# Power_Discrete_-_Features.net
KiCad netlist of a schematic drawn in Altium Designer
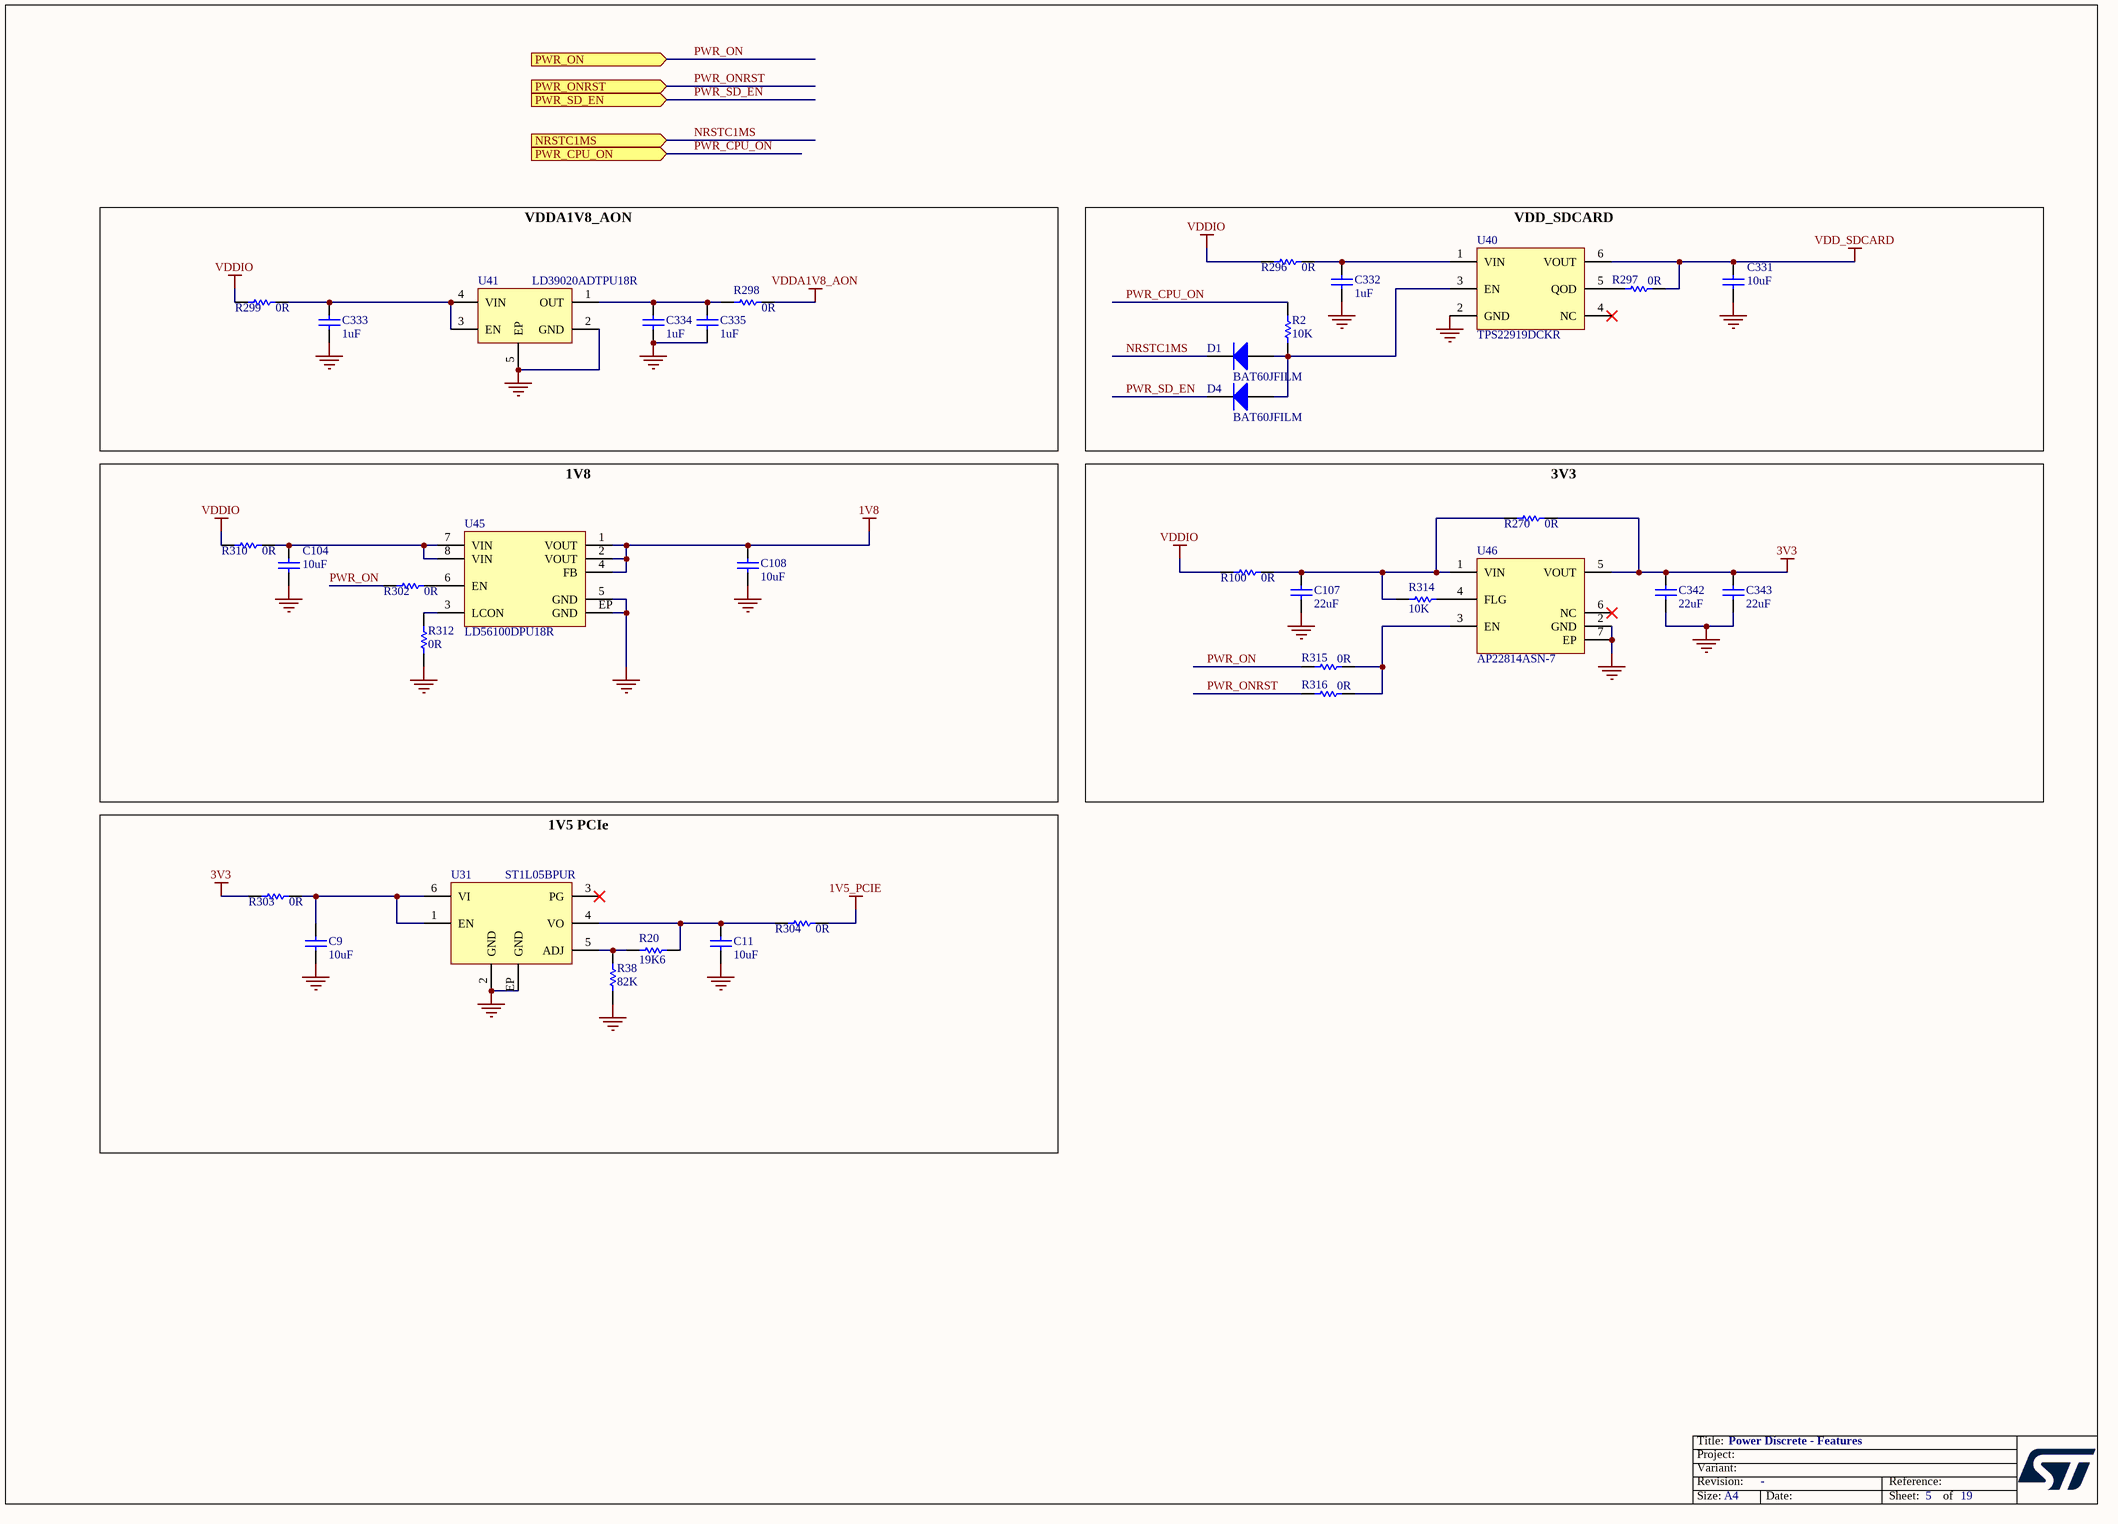
[diagram p0: Power_Discrete - Features.SchDoc]

(export (version "E")
  (design (tool "Eeschema 10.0.6"))
  (components
    (comp (ref "C9")
      (value "10uF")
      (footprint "C0402")
      (description "Capacitor, MLCC, 10uF, 10V, X5R, +/-20%, 0402, T=0.5mm")
      (fields (field (name "INTERNAL_PART_NUMBER") "MCD-01532") (field (name "MANUFACTURER") "MURATA"))
      (libsource (lib "MCD_PARTS_database") (part "Capacitor"))
    )
    (comp (ref "C11")
      (value "10uF")
      (footprint "C0402")
      (description "Capacitor, MLCC, 10uF, 10V, X5R, +/-20%, 0402, T=0.5mm")
      (fields (field (name "INTERNAL_PART_NUMBER") "MCD-01532") (field (name "MANUFACTURER") "MURATA"))
      (libsource (lib "MCD_PARTS_database") (part "Capacitor"))
    )
    (comp (ref "C104")
      (value "10uF")
      (footprint "C0603")
      (description "Capacitor, MLCC, 10uF, 10V, X5R, +/-10%, 0603, T=0,8mm")
      (fields
        (field (name "INTERNAL_PART_NUMBER") "MCD-00099")
        (field (name "MANUFACTURER_PART_NUMBER") "GRM188R61A106KE69D")
      )
      (libsource (lib "MCD_PARTS_database") (part "Capacitor"))
    )
    (comp (ref "C107")
      (value "22uF")
      (footprint "C0603")
      (description "Capacitor, MLCC, 22uF, 6V3, X5R, +/-20%, 0603, T=0,8mm")
      (fields
        (field (name "INTERNAL_PART_NUMBER") "MCD-00100")
        (field (name "MANUFACTURER_PART_NUMBER") "GRM188R60J226MEA0J")
      )
      (libsource (lib "MCD_PARTS_database") (part "Capacitor"))
    )
    (comp (ref "C108")
      (value "10uF")
      (footprint "C0603")
      (description "Capacitor, MLCC, 10uF, 10V, X5R, +/-10%, 0603, T=0.8mm")
      (fields (field (name "INTERNAL_PART_NUMBER") "MCD-00099") (field (name "MANUFACTURER") "MURATA"))
      (libsource (lib "MCD_PARTS_database") (part "Capacitor"))
    )
    (comp (ref "C331")
      (value "10uF")
      (footprint "C0603")
      (description "Capacitor, MLCC, 10uF, 10V, X5R, +/-10%, 0603, T=0,8mm")
      (fields
        (field (name "INTERNAL_PART_NUMBER") "MCD-00099")
        (field (name "MANUFACTURER_PART_NUMBER") "GRM188R61A106KE69D")
      )
      (libsource (lib "MCD_PARTS_database") (part "Capacitor"))
    )
    (comp (ref "C332")
      (value "1uF")
      (footprint "C0402")
      (description "Capacitor, MLCC, 1uF, 25V, X5R, +/-10%, 0402, T=0,5mm")
      (fields
        (field (name "INTERNAL_PART_NUMBER") "MCD-00095")
        (field (name "MANUFACTURER_PART_NUMBER") "GRM155R61E105KA12")
      )
      (libsource (lib "MCD_PARTS_database") (part "Capacitor"))
    )
    (comp (ref "C333")
      (value "1uF")
      (footprint "C0402")
      (description "Capacitor, MLCC, 1uF, 25V, X5R, +/-10%, 0402, T=0.5mm")
      (fields (field (name "INTERNAL_PART_NUMBER") "MCD-00095") (field (name "MANUFACTURER") "MURATA"))
      (libsource (lib "MCD_PARTS_database") (part "Capacitor"))
    )
    (comp (ref "C334")
      (value "1uF")
      (footprint "C0402")
      (description "Capacitor, MLCC, 1uF, 25V, X5R, +/-10%, 0402, T=0.5mm")
      (fields (field (name "INTERNAL_PART_NUMBER") "MCD-00095") (field (name "MANUFACTURER") "MURATA"))
      (libsource (lib "MCD_PARTS_database") (part "Capacitor"))
    )
    (comp (ref "C335")
      (value "1uF")
      (footprint "C0402")
      (description "Capacitor, MLCC, 1uF, 25V, X5R, +/-10%, 0402, T=0.5mm")
      (fields (field (name "INTERNAL_PART_NUMBER") "MCD-00095") (field (name "MANUFACTURER") "MURATA"))
      (libsource (lib "MCD_PARTS_database") (part "Capacitor"))
    )
    (comp (ref "C342")
      (value "22uF")
      (footprint "C0603")
      (description "Capacitor, MLCC, 22uF, 6V3, X5R, +/-20%, 0603, T=0,8mm")
      (fields
        (field (name "INTERNAL_PART_NUMBER") "MCD-00100")
        (field (name "MANUFACTURER_PART_NUMBER") "GRM188R60J226MEA0J")
      )
      (libsource (lib "MCD_PARTS_database") (part "Capacitor"))
    )
    (comp (ref "C343")
      (value "22uF")
      (footprint "C0603")
      (description "Capacitor, MLCC, 22uF, 6V3, X5R, +/-20%, 0603, T=0,8mm")
      (fields
        (field (name "INTERNAL_PART_NUMBER") "MCD-00100")
        (field (name "MANUFACTURER_PART_NUMBER") "GRM188R60J226MEA0J")
      )
      (libsource (lib "MCD_PARTS_database") (part "Capacitor"))
    )
    (comp (ref "D1")
      (value "BAT60JFILM")
      (footprint "DIO_SOD323")
      (fields
        (field (name "INTERNAL_PART_NUMBER") "MCD-00034")
        (field (name "MANUFACTURER") "STMICROELECTRONICS")
        (field (name "BMS_PART_NUMBER") "9151097")
      )
      (libsource (lib "MCD_PARTS_database") (part "BAT60JFILM"))
    )
    (comp (ref "D4")
      (value "BAT60JFILM")
      (footprint "DIO_SOD323")
      (fields
        (field (name "INTERNAL_PART_NUMBER") "MCD-00034")
        (field (name "MANUFACTURER") "STMICROELECTRONICS")
        (field (name "BMS_PART_NUMBER") "9151097")
      )
      (libsource (lib "MCD_PARTS_database") (part "BAT60JFILM"))
    )
    (comp (ref "R2")
      (value "10K")
      (footprint "R0402")
      (description "Resistor,10K,0402,1%,1/16W")
      (fields
        (field (name "INTERNAL_PART_NUMBER") "MCD-00053")
        (field (name "MANUFACTURER_PART_NUMBER") "RC0402FR-0710KL")
      )
      (libsource (lib "MCD_PARTS_database") (part "Resistor"))
    )
    (comp (ref "R20")
      (value "19K6")
      (footprint "R0402")
      (description "Resistor, 19K6, 0402, +/-1%, 1/16W")
      (fields (field (name "INTERNAL_PART_NUMBER") "MCD-00344") (field (name "MANUFACTURER") "YAGEO"))
      (libsource (lib "MCD_PARTS_database") (part "Resistor"))
    )
    (comp (ref "R38")
      (value "82K")
      (footprint "R0402")
      (description "Resistor, 82K, 0402, +/-1%, 1/16W")
      (fields (field (name "INTERNAL_PART_NUMBER") "MCD-00531") (field (name "MANUFACTURER") "YAGEO"))
      (libsource (lib "MCD_PARTS_database") (part "Resistor"))
    )
    (comp (ref "R100")
      (value "0R")
      (footprint "R0603")
      (description "Resistor,0R,0603,5%,1/10W")
      (fields
        (field (name "INTERNAL_PART_NUMBER") "MCD-00056")
        (field (name "MANUFACTURER_PART_NUMBER") "RC0603JR-070RL")
      )
      (libsource (lib "MCD_PARTS_database") (part "Resistor"))
    )
    (comp (ref "R270")
      (value "0R")
      (footprint "R0603")
      (description "Resistor,0R,0603,5%,1/10W")
      (fields
        (field (name "INTERNAL_PART_NUMBER") "MCD-00056")
        (field (name "MANUFACTURER_PART_NUMBER") "RC0603JR-070RL")
      )
      (libsource (lib "MCD_PARTS_database") (part "Resistor"))
    )
    (comp (ref "R296")
      (value "0R")
      (footprint "R0603")
      (description "Resistor,0R,0603,5%,1/10W")
      (fields
        (field (name "INTERNAL_PART_NUMBER") "MCD-00056")
        (field (name "MANUFACTURER_PART_NUMBER") "RC0603JR-070RL")
      )
      (libsource (lib "MCD_PARTS_database") (part "Resistor"))
    )
    (comp (ref "R297")
      (value "0R")
      (footprint "R0402")
      (description "Resistor,0R,0402,5%,1/16W")
      (fields
        (field (name "INTERNAL_PART_NUMBER") "MCD-00052")
        (field (name "MANUFACTURER_PART_NUMBER") "RC0402JR-070RL")
      )
      (libsource (lib "MCD_PARTS_database") (part "Resistor"))
    )
    (comp (ref "R298")
      (value "0R")
      (footprint "R0603")
      (description "Resistor, 0R, 0603, +/- 0.5mR, 1/4W")
      (fields (field (name "INTERNAL_PART_NUMBER") "MCD-00181") (field (name "MANUFACTURER") "ROHM"))
      (libsource (lib "MCD_PARTS_database") (part "Resistor"))
    )
    (comp (ref "R299")
      (value "0R")
      (footprint "R0603")
      (description "Resistor,0R,0603,5%,1/10W")
      (fields
        (field (name "INTERNAL_PART_NUMBER") "MCD-00056")
        (field (name "MANUFACTURER_PART_NUMBER") "RC0603JR-070RL")
      )
      (libsource (lib "MCD_PARTS_database") (part "Resistor"))
    )
    (comp (ref "R302")
      (value "0R")
      (footprint "R0603")
      (description "Resistor,0R,0603,5%,1/10W")
      (fields
        (field (name "INTERNAL_PART_NUMBER") "MCD-00056")
        (field (name "MANUFACTURER_PART_NUMBER") "RC0603JR-070RL")
      )
      (libsource (lib "MCD_PARTS_database") (part "Resistor"))
    )
    (comp (ref "R303")
      (value "0R")
      (footprint "R0603")
      (description "Resistor,0R,0603,5%,1/10W")
      (fields
        (field (name "INTERNAL_PART_NUMBER") "MCD-00056")
        (field (name "MANUFACTURER_PART_NUMBER") "RC0603JR-070RL")
      )
      (libsource (lib "MCD_PARTS_database") (part "Resistor"))
    )
    (comp (ref "R304")
      (value "0R")
      (footprint "R0603")
      (description "Resistor,0R,0603,5%,1/10W")
      (fields
        (field (name "INTERNAL_PART_NUMBER") "MCD-00056")
        (field (name "MANUFACTURER_PART_NUMBER") "RC0603JR-070RL")
      )
      (libsource (lib "MCD_PARTS_database") (part "Resistor"))
    )
    (comp (ref "R310")
      (value "0R")
      (footprint "R0603")
      (description "Resistor,0R,0603,5%,1/10W")
      (fields
        (field (name "INTERNAL_PART_NUMBER") "MCD-00056")
        (field (name "MANUFACTURER_PART_NUMBER") "RC0603JR-070RL")
      )
      (libsource (lib "MCD_PARTS_database") (part "Resistor"))
    )
    (comp (ref "R312")
      (value "0R")
      (footprint "R0402")
      (description "Resistor,0R,0402,5%,1/16W")
      (fields
        (field (name "INTERNAL_PART_NUMBER") "MCD-00052")
        (field (name "MANUFACTURER_PART_NUMBER") "RC0402JR-070RL")
      )
      (libsource (lib "MCD_PARTS_database") (part "Resistor"))
    )
    (comp (ref "R314")
      (value "10K")
      (footprint "R0402")
      (description "Resistor,10K,0402,1%,1/16W")
      (fields
        (field (name "INTERNAL_PART_NUMBER") "MCD-00053")
        (field (name "MANUFACTURER_PART_NUMBER") "RC0402FR-0710KL")
      )
      (libsource (lib "MCD_PARTS_database") (part "Resistor"))
    )
    (comp (ref "R315")
      (value "0R")
      (footprint "R0402")
      (description "Resistor,0R,0402,5%,1/16W")
      (fields
        (field (name "INTERNAL_PART_NUMBER") "MCD-00052")
        (field (name "MANUFACTURER_PART_NUMBER") "RC0402JR-070RL")
      )
      (libsource (lib "MCD_PARTS_database") (part "Resistor"))
    )
    (comp (ref "R316")
      (value "0R")
      (footprint "R0402")
      (description "Resistor,0R,0402,5%,1/16W")
      (fields
        (field (name "INTERNAL_PART_NUMBER") "MCD-00052")
        (field (name "MANUFACTURER_PART_NUMBER") "RC0402JR-070RL")
      )
      (libsource (lib "MCD_PARTS_database") (part "Resistor"))
    )
    (comp (ref "U31")
      (value "ST1L05BPUR")
      (footprint "ICC_DFN6-EPAD_3X3_P095")
      (description "LDO Linear Voltage Regulator IC Positive Adjustable 1 Output Adjustable 1.3A 6-DFN (3x3)")
      (fields (field (name "INTERNAL_PART_NUMBER") "MCD-00581") (field (name "BMS_PART_NUMBER") "9176239"))
      (libsource (lib "MCD_PARTS_database") (part "ST1L05BPUR"))
    )
    (comp (ref "U40")
      (value "TPS22919DCKR")
      (footprint "ICC_SC70-6_DCK_R-PDSO-G6_2X1P25_P065")
      (description "Power Switch, 1.5A , Input 1.6V to 5.5V")
      (fields
        (field (name "INTERNAL_PART_NUMBER") "MCD-02311")
        (field (name "MANUFACTURER") "TEXAS INSTRUMENTS")
      )
      (libsource (lib "MCD_PARTS_database") (part "TPS22919"))
    )
    (comp (ref "U41")
      (value "LD39020ADTPU18R")
      (footprint "REG_XDFN4-EPAD_CASE-711AJ_1X1_H0P4_P065")
      (description "LDO, output 1V8, 200 mA very low quiescent current")
      (fields
        (field (name "INTERNAL_PART_NUMBER") "MCD-02224")
        (field (name "MANUFACTURER") "STMICROELECTRONICS")
      )
      (libsource (lib "MCD_PARTS_database") (part "LD39020"))
    )
    (comp (ref "U45")
      (value "LD56100DPU18R")
      (footprint "ICC_DFN8-EPAD_1P6X1P2_P040_H0P45")
      (description "LDO, Input 1V8 to 5V5, Output 1V8, 1A, ultra-low noise")
      (fields
        (field (name "INTERNAL_PART_NUMBER") "MCD-02937")
        (field (name "MANUFACTURER") "STMICROELECTRONICS")
      )
      (libsource (lib "MCD_PARTS_database") (part "LD56100DPU18R"))
    )
    (comp (ref "U46")
      (value "AP22814ASN-7")
      (description "Power Switch , input 2.7 to 5.5V , 3A")
      (fields
        (field (name "INTERNAL_PART_NUMBER") "MCD-02963")
        (field (name "MANUFACTURER") "DIODES_INCORPORATED")
      )
      (libsource (lib "MCD_PARTS_database") (part "AP22814ASN-7"))
    )
  )
  (nets
    (net (code "1") (name "/NRSTC1MS") (class "Default")
      (node (ref "D1") (pin "2") (pinfunction "K_2") (pintype "passive"))
    )
    (net (code "2") (name "/PWR_CPU_ON") (class "Default")
      (node (ref "R2") (pin "1") (pinfunction "1_1") (pintype "passive"))
    )
    (net (code "3") (name "/PWR_ON") (class "Default")
      (node (ref "R302") (pin "1") (pinfunction "1_1") (pintype "passive"))
      (node (ref "R315") (pin "1") (pinfunction "1_1") (pintype "passive"))
    )
    (net (code "4") (name "/PWR_ONRST") (class "Default")
      (node (ref "R316") (pin "1") (pinfunction "1_1") (pintype "passive"))
    )
    (net (code "5") (name "/PWR_SD_EN") (class "Default")
      (node (ref "D4") (pin "2") (pinfunction "K_2") (pintype "passive"))
    )
    (net (code "6") (name "1V5_PCIE") (class "Default")
      (node (ref "R304") (pin "2") (pinfunction "2_2") (pintype "passive"))
    )
    (net (code "7") (name "1V8") (class "Default")
      (node (ref "C108") (pin "2") (pinfunction "2_2") (pintype "passive"))
      (node (ref "U45") (pin "1") (pinfunction "VOUT_1") (pintype "passive"))
      (node (ref "U45") (pin "2") (pinfunction "VOUT_2") (pintype "passive"))
      (node (ref "U45") (pin "4") (pinfunction "FB_4") (pintype "passive"))
    )
    (net (code "8") (name "3V3") (class "Default")
      (node (ref "C342") (pin "2") (pinfunction "2_2") (pintype "passive"))
      (node (ref "C343") (pin "2") (pinfunction "2_2") (pintype "passive"))
      (node (ref "R270") (pin "2") (pinfunction "2_2") (pintype "passive"))
      (node (ref "R303") (pin "1") (pinfunction "1_1") (pintype "passive"))
      (node (ref "U46") (pin "5") (pinfunction "VOUT_5") (pintype "passive"))
    )
    (net (code "9") (name "GND") (class "Default")
      (node (ref "C104") (pin "1") (pinfunction "1_1") (pintype "passive"))
      (node (ref "C107") (pin "1") (pinfunction "1_1") (pintype "passive"))
      (node (ref "C108") (pin "1") (pinfunction "1_1") (pintype "passive"))
      (node (ref "C11") (pin "1") (pinfunction "1_1") (pintype "passive"))
      (node (ref "C331") (pin "1") (pinfunction "1_1") (pintype "passive"))
      (node (ref "C332") (pin "1") (pinfunction "1_1") (pintype "passive"))
      (node (ref "C333") (pin "1") (pinfunction "1_1") (pintype "passive"))
      (node (ref "C334") (pin "1") (pinfunction "1_1") (pintype "passive"))
      (node (ref "C335") (pin "1") (pinfunction "1_1") (pintype "passive"))
      (node (ref "C342") (pin "1") (pinfunction "1_1") (pintype "passive"))
      (node (ref "C343") (pin "1") (pinfunction "1_1") (pintype "passive"))
      (node (ref "C9") (pin "1") (pinfunction "1_1") (pintype "passive"))
      (node (ref "R312") (pin "1") (pinfunction "1_1") (pintype "passive"))
      (node (ref "R38") (pin "1") (pinfunction "1_1") (pintype "passive"))
      (node (ref "U31") (pin "2") (pinfunction "GND_2") (pintype "passive"))
      (node (ref "U31") (pin "EP") (pinfunction "GND_EP") (pintype "passive"))
      (node (ref "U40") (pin "2") (pinfunction "GND_2") (pintype "passive"))
      (node (ref "U41") (pin "2") (pinfunction "GND_2") (pintype "passive"))
      (node (ref "U41") (pin "5") (pinfunction "EP_5") (pintype "passive"))
      (node (ref "U45") (pin "5") (pinfunction "GND_5") (pintype "passive"))
      (node (ref "U45") (pin "EP") (pinfunction "GND_EP") (pintype "passive"))
      (node (ref "U46") (pin "2") (pinfunction "GND_2") (pintype "passive"))
      (node (ref "U46") (pin "7") (pinfunction "EP_7") (pintype "passive"))
    )
    (net (code "10") (name "Net-(C104-Pad2)") (class "Default")
      (node (ref "C104") (pin "2") (pinfunction "2_2") (pintype "passive"))
      (node (ref "R310") (pin "2") (pinfunction "2_2") (pintype "passive"))
      (node (ref "U45") (pin "7") (pinfunction "VIN_7") (pintype "passive"))
      (node (ref "U45") (pin "8") (pinfunction "VIN_8") (pintype "passive"))
    )
    (net (code "11") (name "Net-(D1-A)") (class "Default")
      (node (ref "D1") (pin "1") (pinfunction "A_1") (pintype "passive"))
      (node (ref "D4") (pin "1") (pinfunction "A_1") (pintype "passive"))
      (node (ref "R2") (pin "2") (pinfunction "2_2") (pintype "passive"))
      (node (ref "U40") (pin "3") (pinfunction "EN_3") (pintype "passive"))
    )
    (net (code "12") (name "Net-(U31-ADJ)") (class "Default")
      (node (ref "R20") (pin "1") (pinfunction "1_1") (pintype "passive"))
      (node (ref "R38") (pin "2") (pinfunction "2_2") (pintype "passive"))
      (node (ref "U31") (pin "5") (pinfunction "ADJ_5") (pintype "passive"))
    )
    (net (code "13") (name "Net-(U31-EN)") (class "Default")
      (node (ref "C9") (pin "2") (pinfunction "2_2") (pintype "passive"))
      (node (ref "R303") (pin "2") (pinfunction "2_2") (pintype "passive"))
      (node (ref "U31") (pin "1") (pinfunction "EN_1") (pintype "passive"))
      (node (ref "U31") (pin "6") (pinfunction "VI_6") (pintype "passive"))
    )
    (net (code "14") (name "Net-(U31-VO)") (class "Default")
      (node (ref "C11") (pin "2") (pinfunction "2_2") (pintype "passive"))
      (node (ref "R20") (pin "2") (pinfunction "2_2") (pintype "passive"))
      (node (ref "R304") (pin "1") (pinfunction "1_1") (pintype "passive"))
      (node (ref "U31") (pin "4") (pinfunction "VO_4") (pintype "passive"))
    )
    (net (code "15") (name "Net-(U40-QOD)") (class "Default")
      (node (ref "R297") (pin "1") (pinfunction "1_1") (pintype "passive"))
      (node (ref "U40") (pin "5") (pinfunction "QOD_5") (pintype "passive"))
    )
    (net (code "16") (name "Net-(U40-VIN)") (class "Default")
      (node (ref "C332") (pin "2") (pinfunction "2_2") (pintype "passive"))
      (node (ref "R296") (pin "2") (pinfunction "2_2") (pintype "passive"))
      (node (ref "U40") (pin "1") (pinfunction "VIN_1") (pintype "passive"))
    )
    (net (code "17") (name "Net-(U41-EN)") (class "Default")
      (node (ref "C333") (pin "2") (pinfunction "2_2") (pintype "passive"))
      (node (ref "R299") (pin "2") (pinfunction "2_2") (pintype "passive"))
      (node (ref "U41") (pin "3") (pinfunction "EN_3") (pintype "passive"))
      (node (ref "U41") (pin "4") (pinfunction "VIN_4") (pintype "passive"))
    )
    (net (code "18") (name "Net-(U41-OUT)") (class "Default")
      (node (ref "C334") (pin "2") (pinfunction "2_2") (pintype "passive"))
      (node (ref "C335") (pin "2") (pinfunction "2_2") (pintype "passive"))
      (node (ref "R298") (pin "1") (pinfunction "1_1") (pintype "passive"))
      (node (ref "U41") (pin "1") (pinfunction "OUT_1") (pintype "passive"))
    )
    (net (code "19") (name "Net-(U45-EN)") (class "Default")
      (node (ref "R302") (pin "2") (pinfunction "2_2") (pintype "passive"))
      (node (ref "U45") (pin "6") (pinfunction "EN_6") (pintype "passive"))
    )
    (net (code "20") (name "Net-(U45-LCON)") (class "Default")
      (node (ref "R312") (pin "2") (pinfunction "2_2") (pintype "passive"))
      (node (ref "U45") (pin "3") (pinfunction "LCON_3") (pintype "passive"))
    )
    (net (code "21") (name "Net-(U46-EN)") (class "Default")
      (node (ref "R315") (pin "2") (pinfunction "2_2") (pintype "passive"))
      (node (ref "R316") (pin "2") (pinfunction "2_2") (pintype "passive"))
      (node (ref "U46") (pin "3") (pinfunction "EN_3") (pintype "passive"))
    )
    (net (code "22") (name "Net-(U46-FLG)") (class "Default")
      (node (ref "R314") (pin "2") (pinfunction "2_2") (pintype "passive"))
      (node (ref "U46") (pin "4") (pinfunction "FLG_4") (pintype "passive"))
    )
    (net (code "23") (name "Net-(U46-VIN)") (class "Default")
      (node (ref "C107") (pin "2") (pinfunction "2_2") (pintype "passive"))
      (node (ref "R100") (pin "2") (pinfunction "2_2") (pintype "passive"))
      (node (ref "R270") (pin "1") (pinfunction "1_1") (pintype "passive"))
      (node (ref "R314") (pin "1") (pinfunction "1_1") (pintype "passive"))
      (node (ref "U46") (pin "1") (pinfunction "VIN_1") (pintype "passive"))
    )
    (net (code "24") (name "VDDA1V8_AON") (class "Default")
      (node (ref "R298") (pin "2") (pinfunction "2_2") (pintype "passive"))
    )
    (net (code "25") (name "VDDIO") (class "Default")
      (node (ref "R100") (pin "1") (pinfunction "1_1") (pintype "passive"))
      (node (ref "R296") (pin "1") (pinfunction "1_1") (pintype "passive"))
      (node (ref "R299") (pin "1") (pinfunction "1_1") (pintype "passive"))
      (node (ref "R310") (pin "1") (pinfunction "1_1") (pintype "passive"))
    )
    (net (code "26") (name "VDD_SDCARD") (class "Default")
      (node (ref "C331") (pin "2") (pinfunction "2_2") (pintype "passive"))
      (node (ref "R297") (pin "2") (pinfunction "2_2") (pintype "passive"))
      (node (ref "U40") (pin "6") (pinfunction "VOUT_6") (pintype "passive"))
    )
    (net (code "27") (name "unconnected-(U31-PG-Pad3)") (class "Default")
      (node (ref "U31") (pin "3") (pinfunction "PG_3") (pintype "passive+no_connect"))
    )
    (net (code "28") (name "unconnected-(U40-NC-Pad4)") (class "Default")
      (node (ref "U40") (pin "4") (pinfunction "NC_4") (pintype "passive+no_connect"))
    )
    (net (code "29") (name "unconnected-(U46-NC-Pad6)") (class "Default")
      (node (ref "U46") (pin "6") (pinfunction "NC_6") (pintype "passive+no_connect"))
    )
  )
)
